# SAMC21_Xplained_Pro_Peripherals.net
KiCad netlist of a schematic drawn in Altium Designer
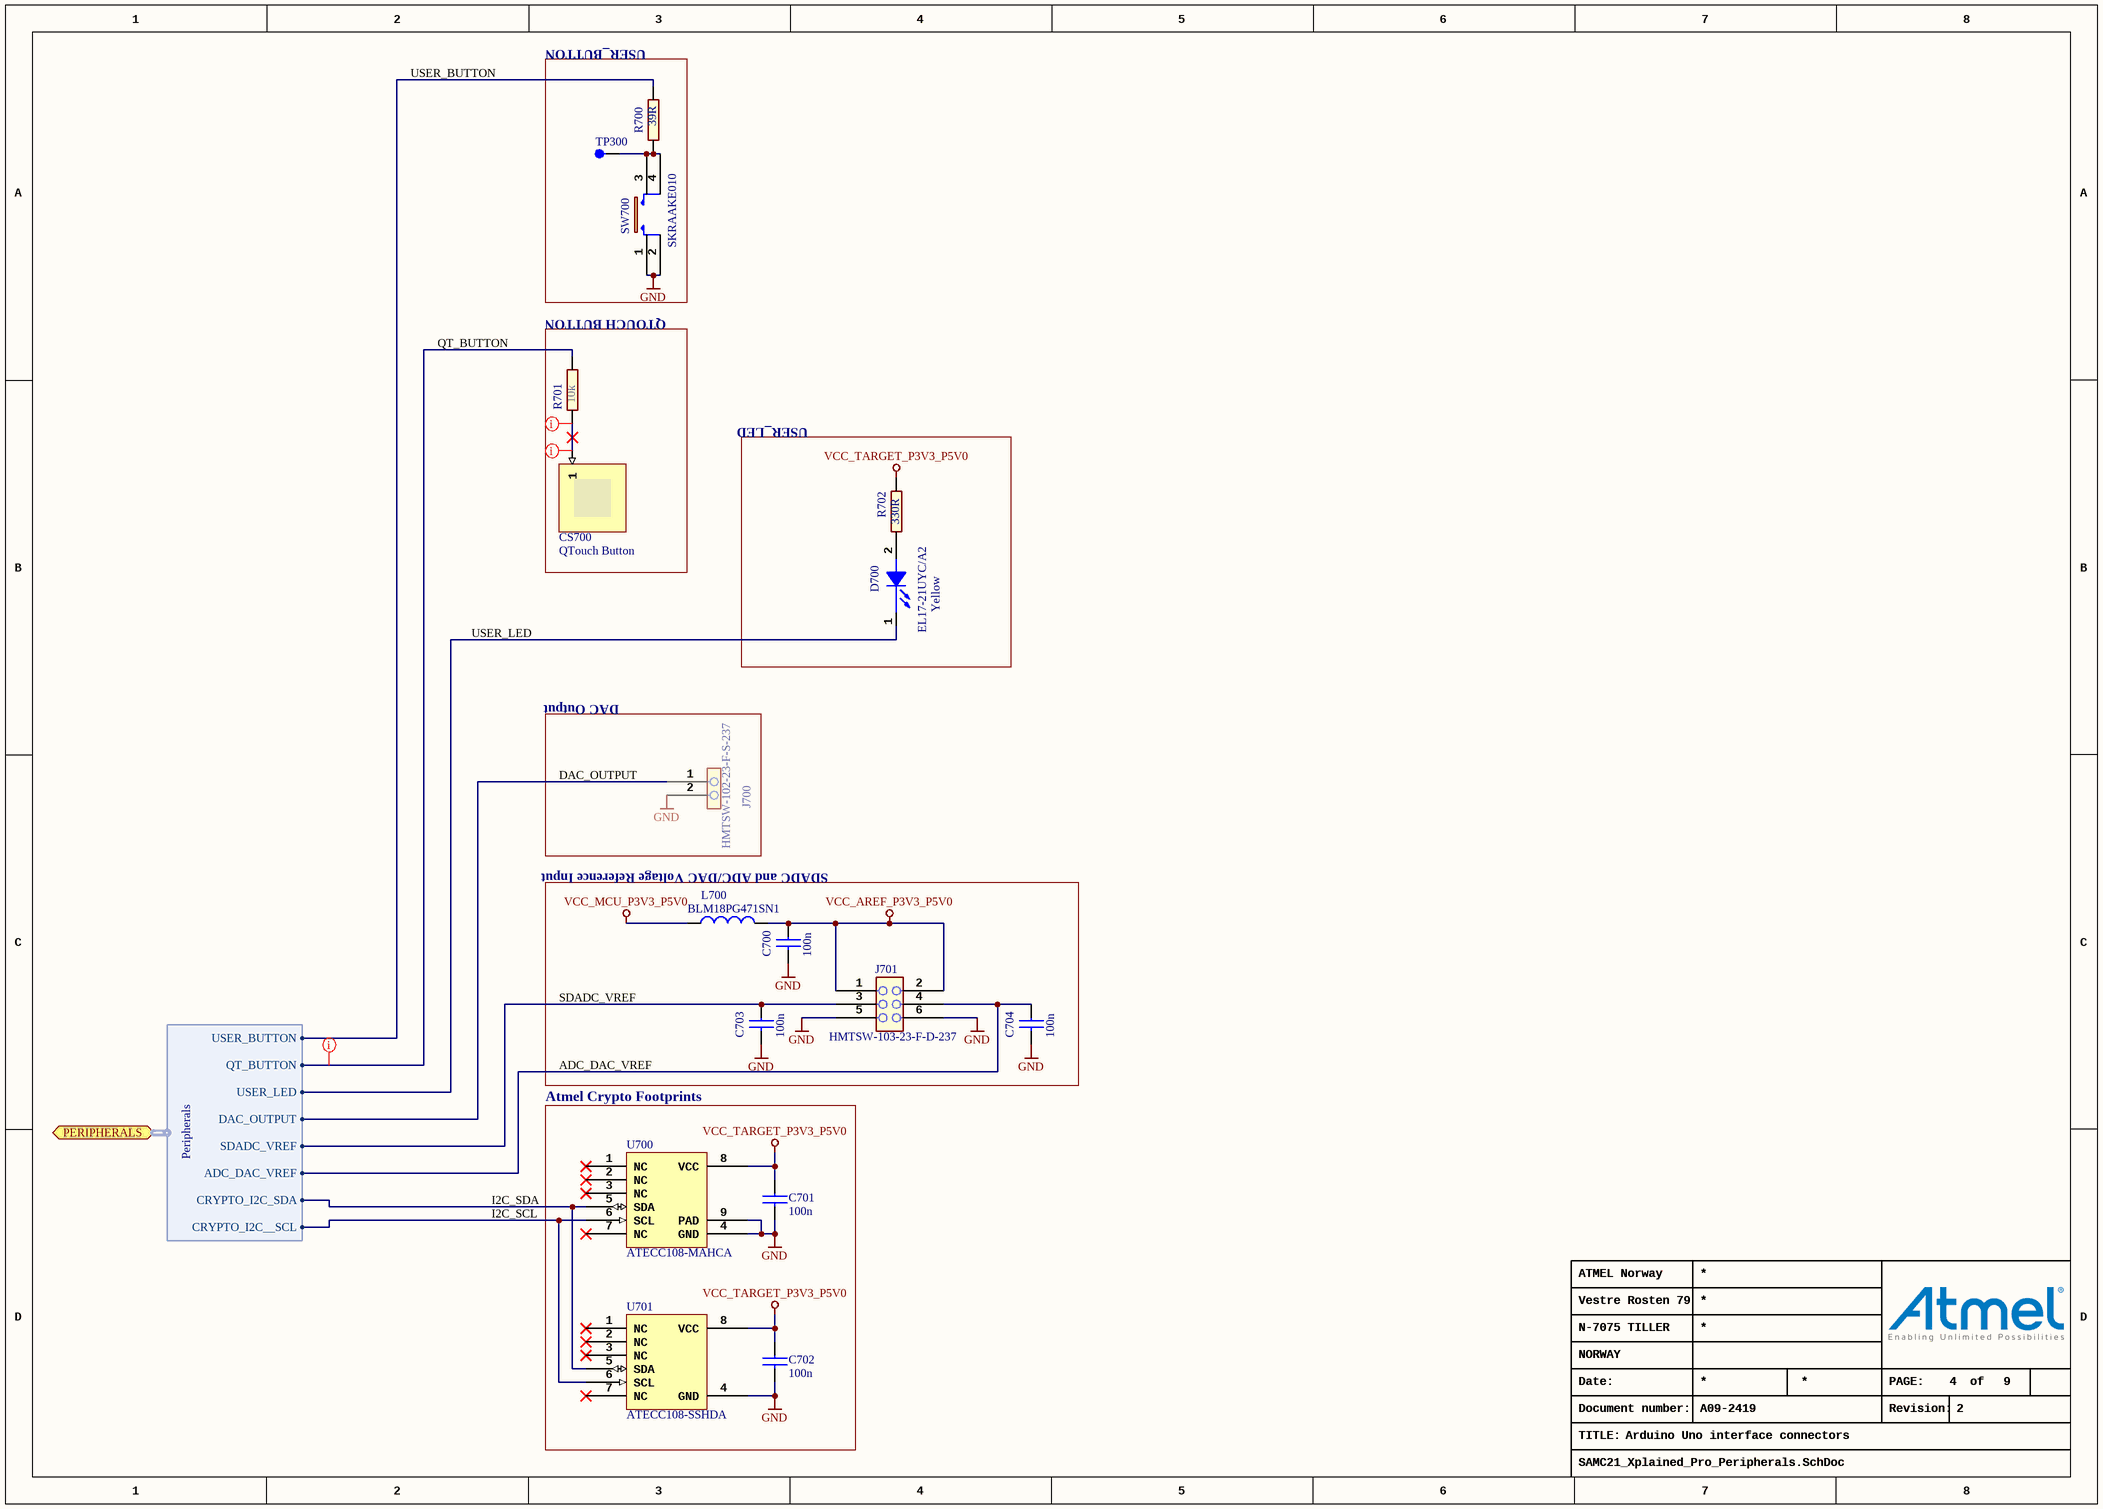
[diagram p0: SAMC21_Xplained_Pro_Peripherals.SchDoc]

(export (version "E")
  (design (tool "Eeschema 10.0.6"))
  (components
    (comp (ref "C700")
      (value "100n")
      (footprint "AP1-00001")
      (description "Ceramic capacitor, SMD 0402, X7R, 16V, +/-10%")
      (fields (field (name "TOLERANCE") "16V, +/-10%") (field (name "MANUFACTURER") "Kemet"))
      (libsource (lib "AltiumDbLib") (part "CAP-NONPOL"))
    )
    (comp (ref "C701")
      (value "100n")
      (footprint "AP1-00001")
      (description "Ceramic capacitor, SMD 0402, X7R, 16V, +/-10%")
      (fields (field (name "TOLERANCE") "16V, +/-10%") (field (name "MANUFACTURER") "Kemet"))
      (libsource (lib "AltiumDbLib") (part "CAP-NONPOL"))
    )
    (comp (ref "C702")
      (value "100n")
      (footprint "AP1-00001")
      (description "Ceramic capacitor, SMD 0402, X7R, 16V, +/-10%")
      (fields (field (name "TOLERANCE") "16V, +/-10%") (field (name "MANUFACTURER") "Kemet"))
      (libsource (lib "AltiumDbLib") (part "CAP-NONPOL"))
    )
    (comp (ref "C703")
      (value "100n")
      (footprint "AP1-00001")
      (description "Ceramic capacitor, SMD 0402, X7R, 16V, +/-10%")
      (fields (field (name "TOLERANCE") "16V, +/-10%") (field (name "MANUFACTURER") "Kemet"))
      (libsource (lib "AltiumDbLib") (part "CAP-NONPOL"))
    )
    (comp (ref "C704")
      (value "100n")
      (footprint "AP1-00001")
      (description "Ceramic capacitor, SMD 0402, X7R, 16V, +/-10%")
      (fields (field (name "TOLERANCE") "16V, +/-10%") (field (name "MANUFACTURER") "Kemet"))
      (libsource (lib "AltiumDbLib") (part "CAP-NONPOL"))
    )
    (comp (ref "CS700") (value "QTouch Button") (libsource (lib "Atmel QTouch") (part "QTouchButton")))
    (comp (ref "D700")
      (value "Yellow")
      (footprint "AP4-00013")
      (description "LED, Yellow, Wave length=591nm, SMD 0805, ±70°")
      (fields
        (field (name "ALTIUM_VALUE") "EL17-21UYC/A2")
        (field (name "MANUFACTURER") "Everlight")
        (field (name "MPN") "17-21UYC/S530-A3/TR8")
      )
      (libsource (lib "AltiumDbLib") (part "LED_12"))
    )
    (comp (ref "J700")
      (value "HMTSW-102-23-F-S-237")
      (footprint "AP8-00733")
      (description "1x2 pin header, 2.54mm pitch, Pin-in-Paste THM")
      (fields (field (name "MANUFACTURER") "SAMTEC") (field (name "Comment") "HEADER 1x2"))
      (libsource (lib "AltiumDbLib") (part "HEADER 1x2"))
    )
    (comp (ref "J701")
      (value "HMTSW-103-23-F-D-237")
      (footprint "AP8-00182")
      (description "2x3 pin header, 2.54mm pitch, Pin-in-Paste THM")
      (fields (field (name "MANUFACTURER") "SAMTEC") (field (name "Comment") "HEADER 2x3"))
      (libsource (lib "AltiumDbLib") (part "HEADER 2x3"))
    )
    (comp (ref "L700")
      (value "BLM18PG471SN1")
      (footprint "AP3-00005")
      (description "SMD RF inductor 0603. Z=470Ohm (@100MHz), Max R(dc)=0.65Ohm, Max current=1A")
      (fields (field (name "TOLERANCE") "±25%") (field (name "MANUFACTURER") "Murata"))
      (libsource (lib "AltiumDbLib") (part "INDUCTOR"))
    )
    (comp (ref "R700")
      (value "39R")
      (footprint "AP2-00000")
      (description "Thick film resistor, SMD 0402, 1/16W, 1%")
      (fields (field (name "TOLERANCE") "1 %") (field (name "Comment") "R2"))
      (libsource (lib "") (part "R2_1"))
    )
    (comp (ref "R701")
      (value "10k")
      (footprint "AP2-00000")
      (description "Thick film resistor, SMD 0402, 1/16W, 1%")
      (fields (field (name "TOLERANCE") "1 %") (field (name "MANUFACTURER") "vishay"))
      (libsource (lib "AltiumDbLib") (part "R2"))
    )
    (comp (ref "R702")
      (value "330R")
      (footprint "AP2-00000")
      (description "Thick film resistor, SMD 0402, 1/16W, 1%")
      (fields (field (name "TOLERANCE") "1 %") (field (name "Comment") "R2"))
      (libsource (lib "AltiumDbLib") (part "R2"))
    )
    (comp (ref "SW700")
      (value "SKRAAKE010")
      (footprint "AP8-00137")
      (description "6.2x6.2 mm SMD tact switch, same as A08-0091 but less force is needed")
      (fields
        (field (name "MANUFACTURER") "ALPS")
        (field (name "Comment") "Can be ordered in low volumes from Mouser")
      )
      (libsource (lib "AltiumDbLib") (part "PUSHBUTTON1"))
    )
    (comp (ref "TP300")
      (value "TESTPOINT")
      (footprint "AP8-00010")
      (description "Single SMD testpad")
      (libsource (lib "AltiumDbLib") (part "TESTPOINT"))
    )
    (comp (ref "U700")
      (value "ATECC108-MAHCA")
      (footprint "AP6-00409")
      (description "Secure authentication and product validation device, EEPROM, I2C, 2.0 - 5.5V, UDFN8")
      (fields (field (name "Comment") "ATECC108_UDFN"))
      (libsource (lib "AltiumDbLib") (part "ATECC108_UDFN"))
    )
    (comp (ref "U701")
      (value "ATECC108-SSHDA")
      (footprint "AP6-00071")
      (description "Secure authentication and product validation device, EEPROM, I2C, 2.0 - 5.5V, SOIC8")
      (fields (field (name "Comment") "ATECC108_SOIC"))
      (libsource (lib "AltiumDbLib") (part "ATECC108_SOIC"))
    )
  )
  (nets
    (net (code "2") (name "/ADC_DAC_VREF") (class "Default")
      (node (ref "C704") (pin "1") (pinfunction "1_1") (pintype "passive"))
      (node (ref "J701") (pin "4") (pinfunction "4_4") (pintype "passive"))
    )
    (net (code "3") (name "/CRYPTO_I2C_SDA") (class "Default")
      (node (ref "U700") (pin "5") (pinfunction "SDA_5") (pintype "bidirectional"))
      (node (ref "U701") (pin "5") (pinfunction "SDA_5") (pintype "bidirectional"))
    )
    (net (code "4") (name "/CRYPTO_I2C__SCL") (class "Default")
      (node (ref "U700") (pin "6") (pinfunction "SCL_6") (pintype "input"))
      (node (ref "U701") (pin "6") (pinfunction "SCL_6") (pintype "input"))
    )
    (net (code "5") (name "/DAC_OUTPUT") (class "Default")
      (node (ref "J700") (pin "1") (pinfunction "1_1") (pintype "passive"))
    )
    (net (code "6") (name "/QT_BUTTON") (class "Default")
      (node (ref "R701") (pin "2") (pinfunction "2_2") (pintype "passive"))
    )
    (net (code "7") (name "/SDADC_VREF") (class "Default")
      (node (ref "C703") (pin "1") (pinfunction "1_1") (pintype "passive"))
      (node (ref "J701") (pin "3") (pinfunction "3_3") (pintype "passive"))
    )
    (net (code "8") (name "/USER_BUTTON") (class "Default")
      (node (ref "R700") (pin "2") (pinfunction "2_2") (pintype "passive"))
    )
    (net (code "9") (name "/USER_LED") (class "Default")
      (node (ref "D700") (pin "1") (pinfunction "CATHODE_1") (pintype "passive"))
    )
    (net (code "11") (name "GND") (class "Default")
      (node (ref "C700") (pin "2") (pinfunction "2_2") (pintype "passive"))
      (node (ref "C701") (pin "2") (pinfunction "2_2") (pintype "passive"))
      (node (ref "C702") (pin "2") (pinfunction "2_2") (pintype "passive"))
      (node (ref "C703") (pin "2") (pinfunction "2_2") (pintype "passive"))
      (node (ref "C704") (pin "2") (pinfunction "2_2") (pintype "passive"))
      (node (ref "J700") (pin "2") (pinfunction "2_2") (pintype "passive"))
      (node (ref "J701") (pin "5") (pinfunction "5_5") (pintype "passive"))
      (node (ref "J701") (pin "6") (pinfunction "6_6") (pintype "passive"))
      (node (ref "SW700") (pin "1") (pinfunction "1_1") (pintype "passive"))
      (node (ref "SW700") (pin "2") (pinfunction "2_2") (pintype "passive"))
      (node (ref "U700") (pin "4") (pinfunction "GND_4") (pintype "power_in"))
      (node (ref "U700") (pin "9") (pinfunction "PAD_9") (pintype "power_in"))
      (node (ref "U701") (pin "4") (pinfunction "GND_4") (pintype "power_in"))
    )
    (net (code "12") (name "Net-(CS700-Pad1)") (class "Default")
      (node (ref "CS700") (pin "1") (pinfunction "1_1") (pintype "input"))
      (node (ref "R701") (pin "1") (pinfunction "1_1") (pintype "passive"))
    )
    (net (code "13") (name "Net-(D700-ANODE)") (class "Default")
      (node (ref "D700") (pin "2") (pinfunction "ANODE_2") (pintype "passive"))
      (node (ref "R702") (pin "1") (pinfunction "1_1") (pintype "passive"))
    )
    (net (code "14") (name "Net-(R700-Pad1)") (class "Default")
      (node (ref "R700") (pin "1") (pinfunction "1_1") (pintype "passive"))
      (node (ref "SW700") (pin "3") (pinfunction "3_3") (pintype "passive"))
      (node (ref "SW700") (pin "4") (pinfunction "4_4") (pintype "passive"))
      (node (ref "TP300") (pin "1") (pinfunction "1_1") (pintype "passive"))
    )
    (net (code "15") (name "VCC_AREF_P3V3_P5V0") (class "Default")
      (node (ref "C700") (pin "1") (pinfunction "1_1") (pintype "passive"))
      (node (ref "J701") (pin "1") (pinfunction "1_1") (pintype "passive"))
      (node (ref "J701") (pin "2") (pinfunction "2_2") (pintype "passive"))
      (node (ref "L700") (pin "2") (pinfunction "2_2") (pintype "passive"))
    )
    (net (code "16") (name "VCC_MCU_P3V3_P5V0") (class "Default")
      (node (ref "L700") (pin "1") (pinfunction "1_1") (pintype "passive"))
    )
    (net (code "17") (name "VCC_TARGET_P3V3_P5V0") (class "Default")
      (node (ref "C701") (pin "1") (pinfunction "1_1") (pintype "passive"))
      (node (ref "C702") (pin "1") (pinfunction "1_1") (pintype "passive"))
      (node (ref "R702") (pin "2") (pinfunction "2_2") (pintype "passive"))
      (node (ref "U700") (pin "8") (pinfunction "VCC_8") (pintype "power_in"))
      (node (ref "U701") (pin "8") (pinfunction "VCC_8") (pintype "power_in"))
    )
    (net (code "18") (name "unconnected-(U700-NC-Pad1)") (class "Default")
      (node (ref "U700") (pin "1") (pinfunction "NC_1") (pintype "passive+no_connect"))
    )
    (net (code "19") (name "unconnected-(U700-NC-Pad2)") (class "Default")
      (node (ref "U700") (pin "2") (pinfunction "NC_2") (pintype "passive+no_connect"))
    )
    (net (code "20") (name "unconnected-(U700-NC-Pad3)") (class "Default")
      (node (ref "U700") (pin "3") (pinfunction "NC_3") (pintype "passive+no_connect"))
    )
    (net (code "21") (name "unconnected-(U700-NC-Pad7)") (class "Default")
      (node (ref "U700") (pin "7") (pinfunction "NC_7") (pintype "passive+no_connect"))
    )
    (net (code "22") (name "unconnected-(U701-NC-Pad1)") (class "Default")
      (node (ref "U701") (pin "1") (pinfunction "NC_1") (pintype "passive+no_connect"))
    )
    (net (code "23") (name "unconnected-(U701-NC-Pad2)") (class "Default")
      (node (ref "U701") (pin "2") (pinfunction "NC_2") (pintype "passive+no_connect"))
    )
    (net (code "24") (name "unconnected-(U701-NC-Pad3)") (class "Default")
      (node (ref "U701") (pin "3") (pinfunction "NC_3") (pintype "passive+no_connect"))
    )
    (net (code "25") (name "unconnected-(U701-NC-Pad7)") (class "Default")
      (node (ref "U701") (pin "7") (pinfunction "NC_7") (pintype "passive+no_connect"))
    )
  )
)
